# RFID_V2.net
KiCad netlist of a schematic drawn in Altium Designer
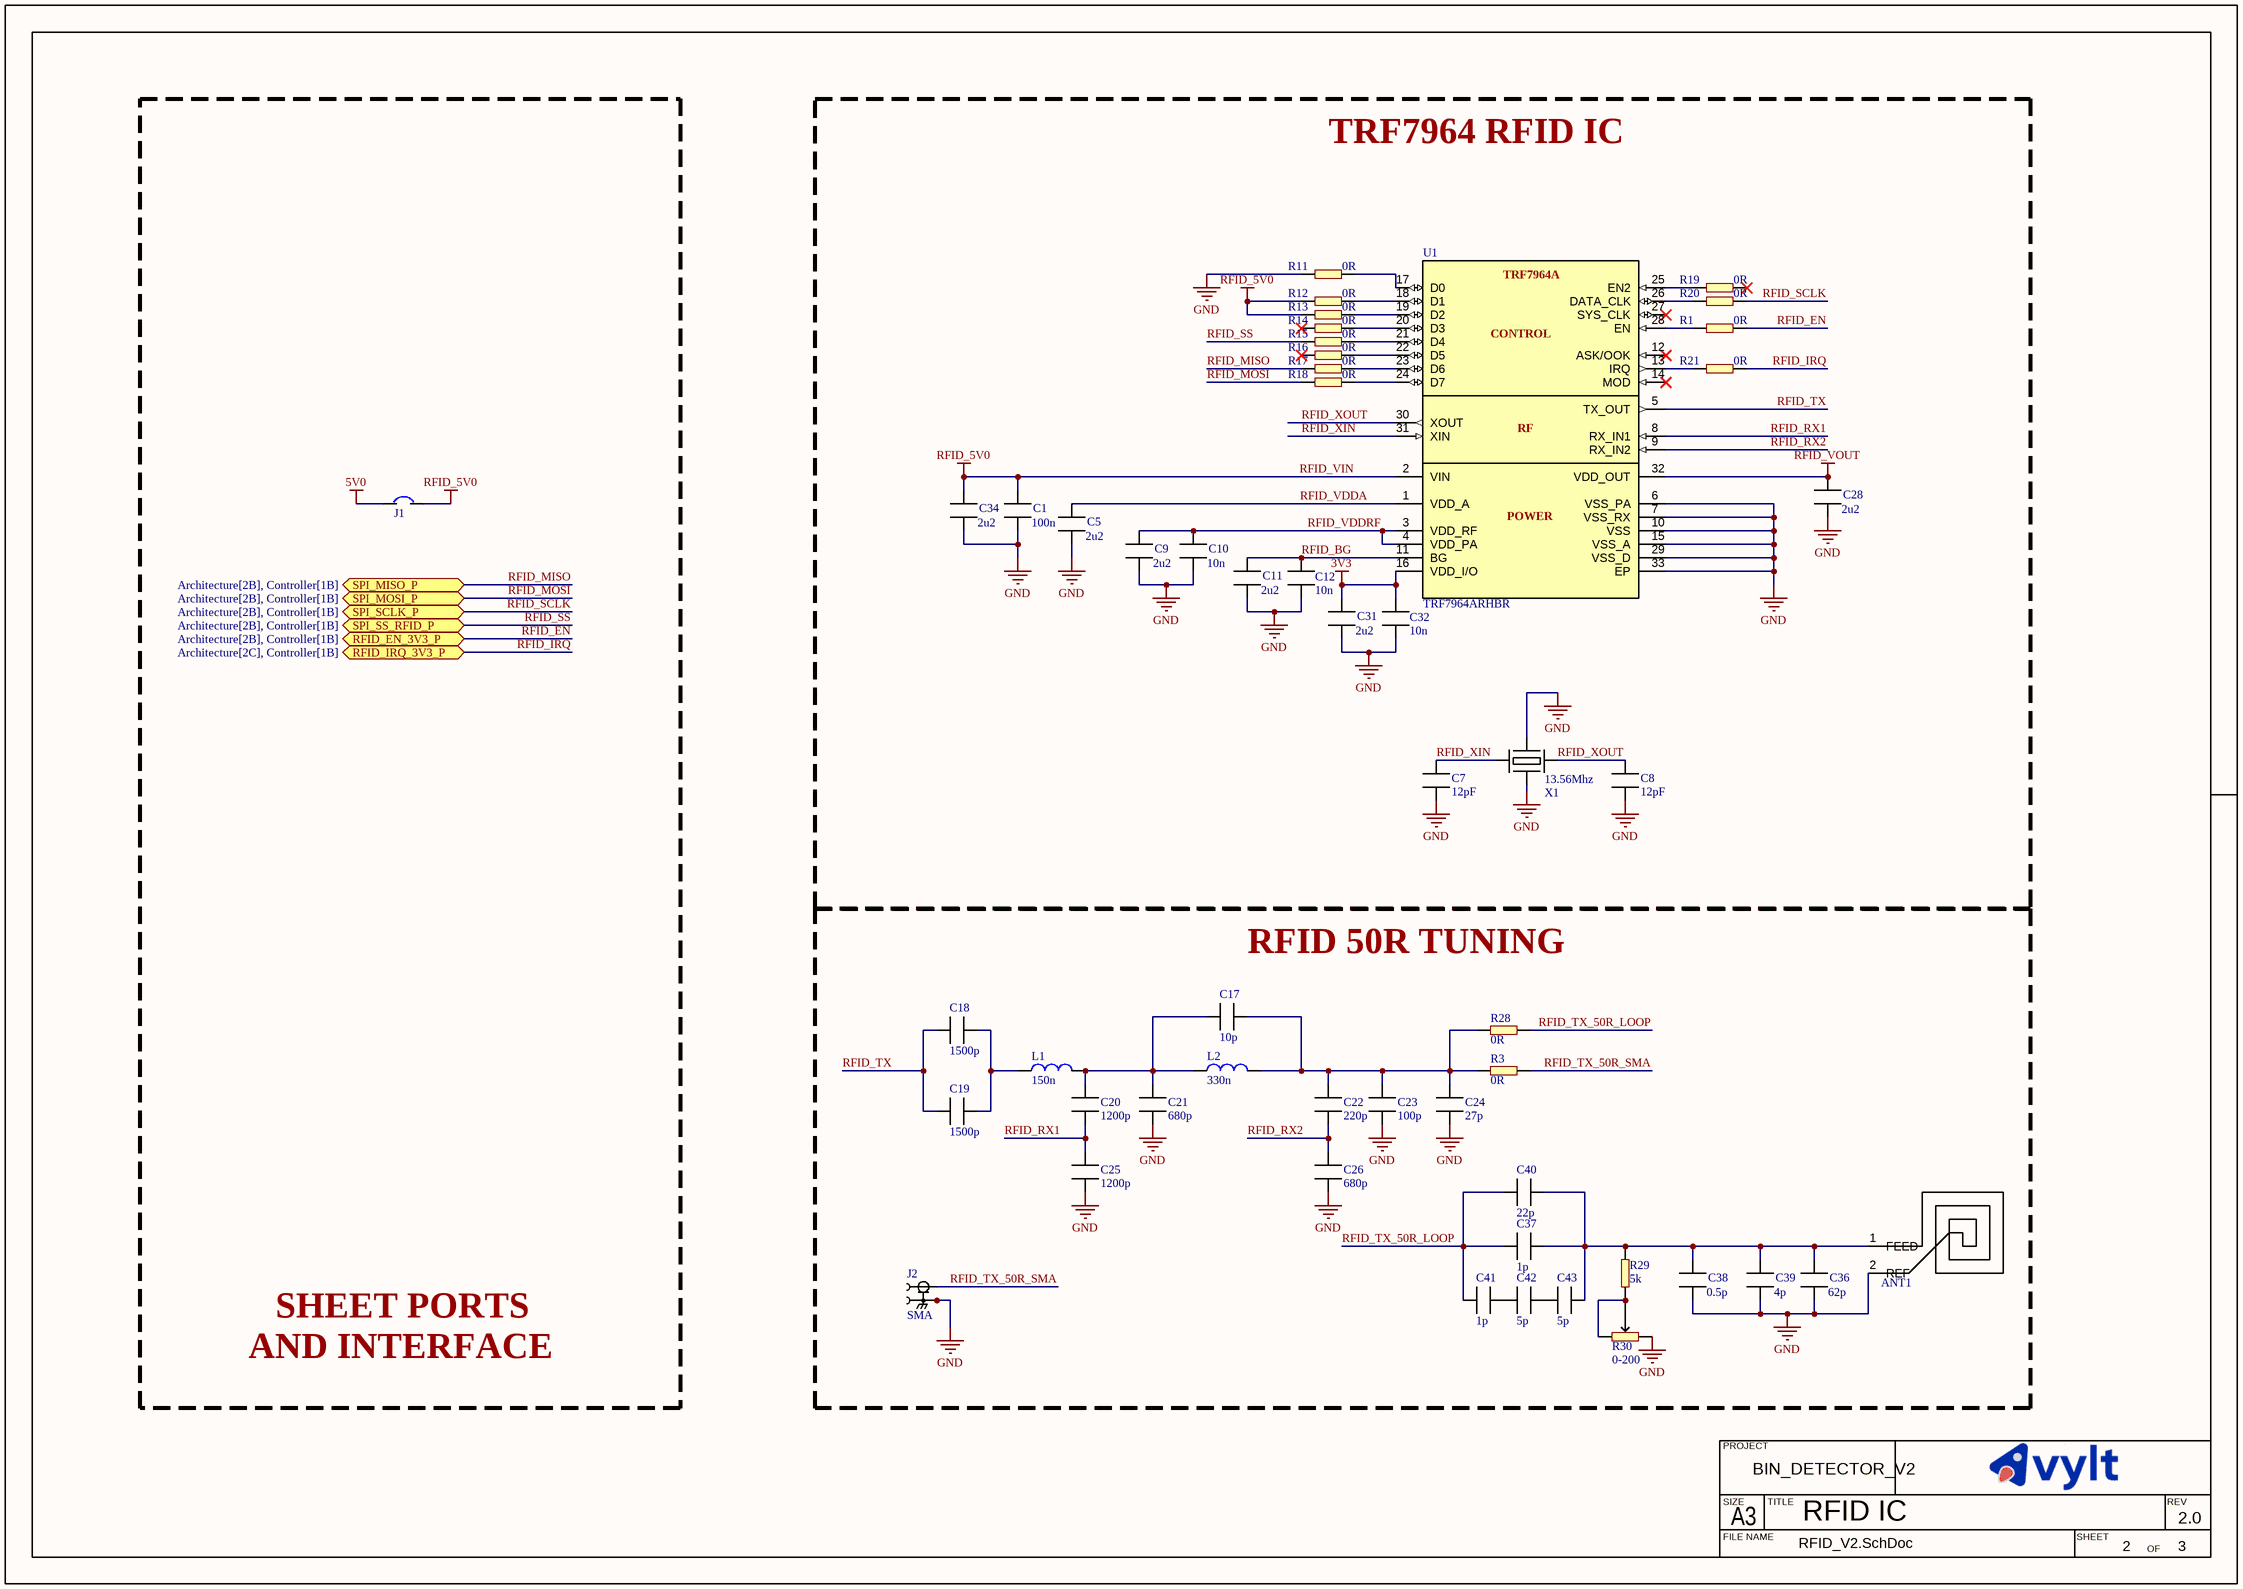
[diagram p0: RFID_V2.SchDoc]

(export (version "E")
  (design (tool "Eeschema 10.0.6"))
  (components
    (comp (ref "ANT1")
      (value "LOOP_ANT_1.51uH")
      (footprint "LOOP_ANT_1.51uH")
      (description "LOOP_ANT_1.51uH_4t_40L_45W_0.4W_0.8P")
      (libsource (lib "Antenna") (part "LOOP_ANT_1.51uH"))
    )
    (comp (ref "C1")
      (value "100n")
      (footprint "CAPC1608X10N")
      (description "MLCC 0603")
      (fields (field (name "Comment") "ERP_102-1"))
      (libsource (lib "Capacitor") (part "MLCC_0603"))
    )
    (comp (ref "C5")
      (value "2u2")
      (footprint "CAPC1608X10N")
      (description "MLCC 0603")
      (fields (field (name "Comment") "ERP_102-1"))
      (libsource (lib "Capacitor") (part "MLCC_0603"))
    )
    (comp (ref "C7")
      (value "12pF")
      (footprint "CAPC1608X10N")
      (description "MLCC 0603")
      (fields (field (name "Comment") "ERP_102-1"))
      (libsource (lib "Capacitor") (part "MLCC_0603"))
    )
    (comp (ref "C8")
      (value "12pF")
      (footprint "CAPC1608X10N")
      (description "MLCC 0603")
      (fields (field (name "Comment") "ERP_102-1"))
      (libsource (lib "Capacitor") (part "MLCC_0603"))
    )
    (comp (ref "C9")
      (value "2u2")
      (footprint "CAPC1608X10N")
      (description "MLCC 0603")
      (fields (field (name "Comment") "ERP_102-1"))
      (libsource (lib "Capacitor") (part "MLCC_0603"))
    )
    (comp (ref "C10")
      (value "10n")
      (footprint "CAPC1608X10N")
      (description "MLCC 0603")
      (fields (field (name "Comment") "ERP_102-1"))
      (libsource (lib "Capacitor") (part "MLCC_0603"))
    )
    (comp (ref "C11")
      (value "2u2")
      (footprint "CAPC1608X10N")
      (description "MLCC 0603")
      (fields (field (name "Comment") "ERP_102-1"))
      (libsource (lib "Capacitor") (part "MLCC_0603"))
    )
    (comp (ref "C12")
      (value "10n")
      (footprint "CAPC1608X10N")
      (description "MLCC 0603")
      (fields (field (name "Comment") "ERP_102-1"))
      (libsource (lib "Capacitor") (part "MLCC_0603"))
    )
    (comp (ref "C17")
      (value "10p")
      (footprint "CAPC1608X10N")
      (description "MLCC 0603")
      (fields (field (name "Comment") "ERP_102-1"))
      (libsource (lib "Capacitor") (part "MLCC_0603"))
    )
    (comp (ref "C18")
      (value "1500p")
      (footprint "CAPC1608X10N")
      (description "MLCC 0603")
      (fields (field (name "Comment") "ERP_102-1"))
      (libsource (lib "Capacitor") (part "MLCC_0603"))
    )
    (comp (ref "C19")
      (value "1500p")
      (footprint "CAPC1608X10N")
      (description "MLCC 0603")
      (fields (field (name "Comment") "ERP_102-1"))
      (libsource (lib "Capacitor") (part "MLCC_0603"))
    )
    (comp (ref "C20")
      (value "1200p")
      (footprint "CAPC1608X10N")
      (description "MLCC 0603")
      (fields (field (name "Comment") "ERP_102-1"))
      (libsource (lib "Capacitor") (part "MLCC_0603"))
    )
    (comp (ref "C21")
      (value "680p")
      (footprint "CAPC1608X10N")
      (description "MLCC 0603")
      (fields (field (name "Comment") "ERP_102-1"))
      (libsource (lib "Capacitor") (part "MLCC_0603"))
    )
    (comp (ref "C22")
      (value "220p")
      (footprint "CAPC1608X10N")
      (description "MLCC 0603")
      (fields (field (name "Comment") "ERP_102-1"))
      (libsource (lib "Capacitor") (part "MLCC_0603"))
    )
    (comp (ref "C23")
      (value "100p")
      (footprint "CAPC1608X10N")
      (description "MLCC 0603")
      (fields (field (name "Comment") "ERP_102-1"))
      (libsource (lib "Capacitor") (part "MLCC_0603"))
    )
    (comp (ref "C24")
      (value "27p")
      (footprint "CAPC1608X10N")
      (description "MLCC 0603")
      (fields (field (name "Comment") "ERP_102-1"))
      (libsource (lib "Capacitor") (part "MLCC_0603"))
    )
    (comp (ref "C25")
      (value "1200p")
      (footprint "CAPC1608X10N")
      (description "MLCC 0603")
      (fields (field (name "Comment") "ERP_102-1"))
      (libsource (lib "Capacitor") (part "MLCC_0603"))
    )
    (comp (ref "C26")
      (value "680p")
      (footprint "CAPC1608X10N")
      (description "MLCC 0603")
      (fields (field (name "Comment") "ERP_102-1"))
      (libsource (lib "Capacitor") (part "MLCC_0603"))
    )
    (comp (ref "C28")
      (value "2u2")
      (footprint "CAPC1608X10N")
      (description "MLCC 0603")
      (fields (field (name "Comment") "ERP_102-1"))
      (libsource (lib "Capacitor") (part "MLCC_0603"))
    )
    (comp (ref "C31")
      (value "2u2")
      (footprint "CAPC1608X10N")
      (description "MLCC 0603")
      (fields (field (name "Comment") "ERP_102-1"))
      (libsource (lib "Capacitor") (part "MLCC_0603"))
    )
    (comp (ref "C32")
      (value "10n")
      (footprint "CAPC1608X10N")
      (description "MLCC 0603")
      (fields (field (name "Comment") "ERP_102-1"))
      (libsource (lib "Capacitor") (part "MLCC_0603"))
    )
    (comp (ref "C34")
      (value "2u2")
      (footprint "CAPC1608X10N")
      (description "MLCC 0603")
      (fields (field (name "Comment") "ERP_102-1"))
      (libsource (lib "Capacitor") (part "MLCC_0603"))
    )
    (comp (ref "C36")
      (value "62p")
      (footprint "CAPC1608X10N")
      (description "Chip Capacitor, 2-Leads, Body 1.60x0.80mm, IPC Medium Density")
      (fields (field (name "Comment") "ERP_102-1"))
      (libsource (lib "Capacitor") (part "MLCC_0603"))
    )
    (comp (ref "C37")
      (value "1p")
      (footprint "CAPC1608X10N")
      (description "Chip Capacitor, 2-Leads, Body 1.60x0.80mm, IPC Medium Density")
      (fields (field (name "Comment") "ERP_102-1"))
      (libsource (lib "Capacitor") (part "MLCC_0603"))
    )
    (comp (ref "C38")
      (value "0.5p")
      (footprint "CAPC1608X10N")
      (description "Chip Capacitor, 2-Leads, Body 1.60x0.80mm, IPC Medium Density")
      (fields (field (name "Comment") "ERP_102-1"))
      (libsource (lib "Capacitor") (part "MLCC_0603"))
    )
    (comp (ref "C39")
      (value "4p")
      (footprint "CAPC1608X10N")
      (description "Chip Capacitor, 2-Leads, Body 1.60x0.80mm, IPC Medium Density")
      (fields (field (name "Comment") "ERP_102-1"))
      (libsource (lib "Capacitor") (part "MLCC_0603"))
    )
    (comp (ref "C40")
      (value "22p")
      (footprint "CAPC1608X10N")
      (description "Chip Capacitor, 2-Leads, Body 1.60x0.80mm, IPC Medium Density")
      (fields (field (name "Comment") "ERP_102-1"))
      (libsource (lib "Capacitor") (part "MLCC_0603"))
    )
    (comp (ref "C41")
      (value "1p")
      (footprint "CAPC1608X10N")
      (description "Chip Capacitor, 2-Leads, Body 1.60x0.80mm, IPC Medium Density")
      (fields (field (name "Comment") "ERP_102-1"))
      (libsource (lib "Capacitor") (part "MLCC_0603"))
    )
    (comp (ref "C42")
      (value "5p")
      (footprint "CAPC1608X10N")
      (description "Chip Capacitor, 2-Leads, Body 1.60x0.80mm, IPC Medium Density")
      (fields (field (name "Comment") "ERP_102-1"))
      (libsource (lib "Capacitor") (part "MLCC_0603"))
    )
    (comp (ref "C43")
      (value "5p")
      (footprint "CAPC1608X10N")
      (description "Chip Capacitor, 2-Leads, Body 1.60x0.80mm, IPC Medium Density")
      (fields (field (name "Comment") "ERP_102-1"))
      (libsource (lib "Capacitor") (part "MLCC_0603"))
    )
    (comp (ref "J1")
      (value "Jumper_2P")
      (footprint "Jumper_2P")
      (description "Jumper 2 Pins")
      (libsource (lib "Jumper") (part "Jumper_2P"))
    )
    (comp (ref "J2")
      (value "SMA")
      (footprint "SMA_TopEntry_50R")
      (description "SMA STR PCB SKT GZD")
      (fields (field (name "Comment") "SMA_TopEntry_50R"))
      (libsource (lib "RF_Connector") (part "SMA_TopEntry_50R"))
    )
    (comp (ref "L1")
      (value "150n")
      (footprint "IND_1008")
      (description "IND_1008")
      (fields (field (name "Comment") "ERP_103-3"))
      (libsource (lib "Inductor") (part "IND_1008"))
    )
    (comp (ref "L2")
      (value "330n")
      (footprint "IND_1008")
      (description "IND_1008")
      (fields (field (name "Comment") "ERP_103-3"))
      (libsource (lib "Inductor") (part "IND_1008"))
    )
    (comp (ref "R1")
      (value "0R")
      (footprint "RES_0603")
      (description "RES_0603")
      (fields (field (name "Comment") "ERP_101-1"))
      (libsource (lib "Resistor") (part "RES_0603"))
    )
    (comp (ref "R3")
      (value "0R")
      (footprint "RES_0603")
      (description "RES_0603")
      (fields (field (name "Comment") "ERP_101-1"))
      (libsource (lib "Resistor") (part "RES_0603"))
    )
    (comp (ref "R11")
      (value "0R")
      (footprint "RES_0603")
      (description "RES_0603")
      (fields (field (name "Comment") "ERP_101-1"))
      (libsource (lib "Resistor") (part "RES_0603"))
    )
    (comp (ref "R12")
      (value "0R")
      (footprint "RES_0603")
      (description "RES_0603")
      (fields (field (name "Comment") "ERP_101-1"))
      (libsource (lib "Resistor") (part "RES_0603"))
    )
    (comp (ref "R13")
      (value "0R")
      (footprint "RES_0603")
      (description "RES_0603")
      (fields (field (name "Comment") "ERP_101-1"))
      (libsource (lib "Resistor") (part "RES_0603"))
    )
    (comp (ref "R14")
      (value "0R")
      (footprint "RES_0603")
      (description "RES_0603")
      (fields (field (name "Comment") "ERP_101-1"))
      (libsource (lib "Resistor") (part "RES_0603"))
    )
    (comp (ref "R15")
      (value "0R")
      (footprint "RES_0603")
      (description "RES_0603")
      (fields (field (name "Comment") "ERP_101-1"))
      (libsource (lib "Resistor") (part "RES_0603"))
    )
    (comp (ref "R16")
      (value "0R")
      (footprint "RES_0603")
      (description "RES_0603")
      (fields (field (name "Comment") "ERP_101-1"))
      (libsource (lib "Resistor") (part "RES_0603"))
    )
    (comp (ref "R17")
      (value "0R")
      (footprint "RES_0603")
      (description "RES_0603")
      (fields (field (name "Comment") "ERP_101-1"))
      (libsource (lib "Resistor") (part "RES_0603"))
    )
    (comp (ref "R18")
      (value "0R")
      (footprint "RES_0603")
      (description "RES_0603")
      (fields (field (name "Comment") "ERP_101-1"))
      (libsource (lib "Resistor") (part "RES_0603"))
    )
    (comp (ref "R19")
      (value "0R")
      (footprint "RES_0603")
      (description "RES_0603")
      (fields (field (name "Comment") "ERP_101-1"))
      (libsource (lib "Resistor") (part "RES_0603"))
    )
    (comp (ref "R20")
      (value "0R")
      (footprint "RES_0603")
      (description "RES_0603")
      (fields (field (name "Comment") "ERP_101-1"))
      (libsource (lib "Resistor") (part "RES_0603"))
    )
    (comp (ref "R21")
      (value "0R")
      (footprint "RES_0603")
      (description "RES_0603")
      (fields (field (name "Comment") "ERP_101-1"))
      (libsource (lib "Resistor") (part "RES_0603"))
    )
    (comp (ref "R28")
      (value "0R")
      (footprint "RES_0603")
      (description "RES_0603")
      (fields (field (name "Comment") "ERP_101-1"))
      (libsource (lib "Resistor") (part "RES_0603"))
    )
    (comp (ref "R29")
      (value "5k")
      (footprint "RES_0603")
      (description "RES_0603")
      (fields (field (name "Comment") "ERP_101-1"))
      (libsource (lib "") (part "RES_0603_1"))
    )
    (comp (ref "R30")
      (value "0-200")
      (footprint "RES_VAR_3361P")
      (description "TRIMMER 200 OHM 0.5W GW TOP ADJ")
      (fields (field (name "Comment") "ERP_101-1"))
      (libsource (lib "Resistor") (part "RES_VAR_3361P"))
    )
    (comp (ref "U1")
      (value "TRF7964ARHBR")
      (footprint "RHB32_3P45X3P45_TEX")
      (description "IC RFID READER 13.56MHZ 32VQFN")
      (fields (field (name "Comment") "ERP_121-4"))
      (libsource (lib "RF-IC") (part "TRF7964A"))
    )
    (comp (ref "X1")
      (value "13.56Mhz")
      (footprint "CRYS_L3.2_W2.5")
      (description "CRYS_L3.2_W2.5")
      (fields (field (name "Comment") "ERP_111-1"))
      (libsource (lib "Crystal") (part "CRYS_L3.2_W2.5"))
    )
  )
  (nets
    (net (code "1") (name "/RFID_BG") (class "Default")
      (node (ref "C11") (pin "1") (pinfunction "1_1") (pintype "passive"))
      (node (ref "C12") (pin "1") (pinfunction "1_1") (pintype "passive"))
      (node (ref "U1") (pin "11") (pinfunction "BG_11") (pintype "passive"))
    )
    (net (code "2") (name "/RFID_EN") (class "Default")
      (node (ref "R1") (pin "1") (pinfunction "1_1") (pintype "passive"))
    )
    (net (code "3") (name "/RFID_IRQ") (class "Default")
      (node (ref "R21") (pin "1") (pinfunction "1_1") (pintype "passive"))
    )
    (net (code "4") (name "/RFID_MISO") (class "Default")
      (node (ref "R17") (pin "2") (pinfunction "2_2") (pintype "passive"))
    )
    (net (code "5") (name "/RFID_MOSI") (class "Default")
      (node (ref "R18") (pin "2") (pinfunction "2_2") (pintype "passive"))
    )
    (net (code "6") (name "/RFID_RX1") (class "Default")
      (node (ref "C20") (pin "1") (pinfunction "1_1") (pintype "passive"))
      (node (ref "C25") (pin "2") (pinfunction "2_2") (pintype "passive"))
      (node (ref "U1") (pin "8") (pinfunction "RX_IN1_8") (pintype "input"))
    )
    (net (code "7") (name "/RFID_RX2") (class "Default")
      (node (ref "C22") (pin "1") (pinfunction "1_1") (pintype "passive"))
      (node (ref "C26") (pin "2") (pinfunction "2_2") (pintype "passive"))
      (node (ref "U1") (pin "9") (pinfunction "RX_IN2_9") (pintype "input"))
    )
    (net (code "8") (name "/RFID_SCLK") (class "Default")
      (node (ref "R20") (pin "1") (pinfunction "1_1") (pintype "passive"))
    )
    (net (code "9") (name "/RFID_SS") (class "Default")
      (node (ref "R15") (pin "2") (pinfunction "2_2") (pintype "passive"))
    )
    (net (code "10") (name "/RFID_TX") (class "Default")
      (node (ref "C18") (pin "1") (pinfunction "1_1") (pintype "passive"))
      (node (ref "C19") (pin "1") (pinfunction "1_1") (pintype "passive"))
      (node (ref "U1") (pin "5") (pinfunction "TX_OUT_5") (pintype "output"))
    )
    (net (code "11") (name "/RFID_TX_50R_LOOP") (class "Default")
      (node (ref "C37") (pin "1") (pinfunction "1_1") (pintype "passive"))
      (node (ref "C40") (pin "1") (pinfunction "1_1") (pintype "passive"))
      (node (ref "C41") (pin "1") (pinfunction "1_1") (pintype "passive"))
      (node (ref "R28") (pin "1") (pinfunction "1_1") (pintype "passive"))
    )
    (net (code "12") (name "/RFID_TX_50R_SMA") (class "Default")
      (node (ref "J2") (pin "1") (pinfunction "1_1") (pintype "passive"))
      (node (ref "R3") (pin "1") (pinfunction "1_1") (pintype "passive"))
    )
    (net (code "13") (name "/RFID_VDDA") (class "Default")
      (node (ref "C5") (pin "1") (pinfunction "1_1") (pintype "passive"))
      (node (ref "U1") (pin "1") (pinfunction "VDD_A_1") (pintype "passive"))
    )
    (net (code "14") (name "/RFID_VDDRF") (class "Default")
      (node (ref "C10") (pin "1") (pinfunction "1_1") (pintype "passive"))
      (node (ref "C9") (pin "1") (pinfunction "1_1") (pintype "passive"))
      (node (ref "U1") (pin "3") (pinfunction "VDD_RF_3") (pintype "passive"))
      (node (ref "U1") (pin "4") (pinfunction "VDD_PA_4") (pintype "passive"))
    )
    (net (code "15") (name "/RFID_XIN") (class "Default")
      (node (ref "C7") (pin "1") (pinfunction "1_1") (pintype "passive"))
      (node (ref "U1") (pin "31") (pinfunction "XIN_31") (pintype "input"))
      (node (ref "X1") (pin "1") (pinfunction "1_1") (pintype "passive"))
    )
    (net (code "16") (name "/RFID_XOUT") (class "Default")
      (node (ref "C8") (pin "1") (pinfunction "1_1") (pintype "passive"))
      (node (ref "U1") (pin "30") (pinfunction "XOUT_30") (pintype "output"))
      (node (ref "X1") (pin "3") (pinfunction "3_3") (pintype "passive"))
    )
    (net (code "17") (name "3V3") (class "Default")
      (node (ref "C31") (pin "1") (pinfunction "1_1") (pintype "passive"))
      (node (ref "C32") (pin "1") (pinfunction "1_1") (pintype "passive"))
      (node (ref "U1") (pin "16") (pinfunction "VDD_I/O_16") (pintype "passive"))
    )
    (net (code "18") (name "5V0") (class "Default") (node (ref "J1") (pin "1") (pintype "passive")))
    (net (code "19") (name "GND") (class "Default")
      (node (ref "ANT1") (pin "2") (pinfunction "REF_2") (pintype "passive"))
      (node (ref "C1") (pin "2") (pinfunction "2_2") (pintype "passive"))
      (node (ref "C10") (pin "2") (pinfunction "2_2") (pintype "passive"))
      (node (ref "C11") (pin "2") (pinfunction "2_2") (pintype "passive"))
      (node (ref "C12") (pin "2") (pinfunction "2_2") (pintype "passive"))
      (node (ref "C21") (pin "1") (pinfunction "1_1") (pintype "passive"))
      (node (ref "C23") (pin "1") (pinfunction "1_1") (pintype "passive"))
      (node (ref "C24") (pin "1") (pinfunction "1_1") (pintype "passive"))
      (node (ref "C25") (pin "1") (pinfunction "1_1") (pintype "passive"))
      (node (ref "C26") (pin "1") (pinfunction "1_1") (pintype "passive"))
      (node (ref "C28") (pin "2") (pinfunction "2_2") (pintype "passive"))
      (node (ref "C31") (pin "2") (pinfunction "2_2") (pintype "passive"))
      (node (ref "C32") (pin "2") (pinfunction "2_2") (pintype "passive"))
      (node (ref "C34") (pin "2") (pinfunction "2_2") (pintype "passive"))
      (node (ref "C36") (pin "2") (pinfunction "2_2") (pintype "passive"))
      (node (ref "C38") (pin "2") (pinfunction "2_2") (pintype "passive"))
      (node (ref "C39") (pin "2") (pinfunction "2_2") (pintype "passive"))
      (node (ref "C5") (pin "2") (pinfunction "2_2") (pintype "passive"))
      (node (ref "C7") (pin "2") (pinfunction "2_2") (pintype "passive"))
      (node (ref "C8") (pin "2") (pinfunction "2_2") (pintype "passive"))
      (node (ref "C9") (pin "2") (pinfunction "2_2") (pintype "passive"))
      (node (ref "J2") (pin "2") (pinfunction "2_2") (pintype "passive"))
      (node (ref "J2") (pin "3") (pinfunction "3_3") (pintype "passive"))
      (node (ref "J2") (pin "4") (pinfunction "4_4") (pintype "passive"))
      (node (ref "J2") (pin "5") (pinfunction "5_5") (pintype "passive"))
      (node (ref "R11") (pin "2") (pinfunction "2_2") (pintype "passive"))
      (node (ref "R30") (pin "1") (pinfunction "1_1") (pintype "passive"))
      (node (ref "U1") (pin "10") (pinfunction "VSS_10") (pintype "passive"))
      (node (ref "U1") (pin "15") (pinfunction "VSS_A_15") (pintype "passive"))
      (node (ref "U1") (pin "29") (pinfunction "VSS_D_29") (pintype "passive"))
      (node (ref "U1") (pin "33") (pinfunction "EP_33") (pintype "passive"))
      (node (ref "U1") (pin "6") (pinfunction "VSS_PA_6") (pintype "passive"))
      (node (ref "U1") (pin "7") (pinfunction "VSS_RX_7") (pintype "passive"))
      (node (ref "X1") (pin "2") (pinfunction "2_2") (pintype "passive"))
      (node (ref "X1") (pin "4") (pinfunction "4_4") (pintype "passive"))
    )
    (net (code "20") (name "Net-(ANT1-FEED)") (class "Default")
      (node (ref "ANT1") (pin "1") (pinfunction "FEED_1") (pintype "passive"))
      (node (ref "C36") (pin "1") (pinfunction "1_1") (pintype "passive"))
      (node (ref "C37") (pin "2") (pinfunction "2_2") (pintype "passive"))
      (node (ref "C38") (pin "1") (pinfunction "1_1") (pintype "passive"))
      (node (ref "C39") (pin "1") (pinfunction "1_1") (pintype "passive"))
      (node (ref "C40") (pin "2") (pinfunction "2_2") (pintype "passive"))
      (node (ref "C43") (pin "2") (pinfunction "2_2") (pintype "passive"))
      (node (ref "R29") (pin "2") (pinfunction "2_2") (pintype "passive"))
    )
    (net (code "21") (name "Net-(C17-Pad1)") (class "Default")
      (node (ref "C17") (pin "1") (pinfunction "1_1") (pintype "passive"))
      (node (ref "C22") (pin "2") (pinfunction "2_2") (pintype "passive"))
      (node (ref "C23") (pin "2") (pinfunction "2_2") (pintype "passive"))
      (node (ref "C24") (pin "2") (pinfunction "2_2") (pintype "passive"))
      (node (ref "L2") (pin "2") (pinfunction "2_2") (pintype "passive"))
      (node (ref "R28") (pin "2") (pinfunction "2_2") (pintype "passive"))
      (node (ref "R3") (pin "2") (pinfunction "2_2") (pintype "passive"))
    )
    (net (code "22") (name "Net-(C17-Pad2)") (class "Default")
      (node (ref "C17") (pin "2") (pinfunction "2_2") (pintype "passive"))
      (node (ref "C20") (pin "2") (pinfunction "2_2") (pintype "passive"))
      (node (ref "C21") (pin "2") (pinfunction "2_2") (pintype "passive"))
      (node (ref "L1") (pin "2") (pinfunction "2_2") (pintype "passive"))
      (node (ref "L2") (pin "1") (pinfunction "1_1") (pintype "passive"))
    )
    (net (code "23") (name "Net-(C18-Pad2)") (class "Default")
      (node (ref "C18") (pin "2") (pinfunction "2_2") (pintype "passive"))
      (node (ref "C19") (pin "2") (pinfunction "2_2") (pintype "passive"))
      (node (ref "L1") (pin "1") (pinfunction "1_1") (pintype "passive"))
    )
    (net (code "24") (name "Net-(C41-Pad2)") (class "Default")
      (node (ref "C41") (pin "2") (pinfunction "2_2") (pintype "passive"))
      (node (ref "C42") (pin "1") (pinfunction "1_1") (pintype "passive"))
    )
    (net (code "25") (name "Net-(C42-Pad2)") (class "Default")
      (node (ref "C42") (pin "2") (pinfunction "2_2") (pintype "passive"))
      (node (ref "C43") (pin "1") (pinfunction "1_1") (pintype "passive"))
    )
    (net (code "26") (name "Net-(R29-Pad1)") (class "Default")
      (node (ref "R29") (pin "1") (pinfunction "1_1") (pintype "passive"))
      (node (ref "R30") (pin "2") (pinfunction "2_2") (pintype "passive"))
      (node (ref "R30") (pin "3") (pinfunction "3_3") (pintype "passive"))
    )
    (net (code "27") (name "Net-(U1-D0)") (class "Default")
      (node (ref "R11") (pin "1") (pinfunction "1_1") (pintype "passive"))
      (node (ref "U1") (pin "17") (pinfunction "D0_17") (pintype "bidirectional"))
    )
    (net (code "28") (name "Net-(U1-D1)") (class "Default")
      (node (ref "R12") (pin "1") (pinfunction "1_1") (pintype "passive"))
      (node (ref "U1") (pin "18") (pinfunction "D1_18") (pintype "bidirectional"))
    )
    (net (code "29") (name "Net-(U1-D2)") (class "Default")
      (node (ref "R13") (pin "1") (pinfunction "1_1") (pintype "passive"))
      (node (ref "U1") (pin "19") (pinfunction "D2_19") (pintype "bidirectional"))
    )
    (net (code "30") (name "Net-(U1-D3)") (class "Default")
      (node (ref "R14") (pin "1") (pinfunction "1_1") (pintype "passive"))
      (node (ref "U1") (pin "20") (pinfunction "D3_20") (pintype "bidirectional"))
    )
    (net (code "31") (name "Net-(U1-D4)") (class "Default")
      (node (ref "R15") (pin "1") (pinfunction "1_1") (pintype "passive"))
      (node (ref "U1") (pin "21") (pinfunction "D4_21") (pintype "bidirectional"))
    )
    (net (code "32") (name "Net-(U1-D5)") (class "Default")
      (node (ref "R16") (pin "1") (pinfunction "1_1") (pintype "passive"))
      (node (ref "U1") (pin "22") (pinfunction "D5_22") (pintype "bidirectional"))
    )
    (net (code "33") (name "Net-(U1-D6)") (class "Default")
      (node (ref "R17") (pin "1") (pinfunction "1_1") (pintype "passive"))
      (node (ref "U1") (pin "23") (pinfunction "D6_23") (pintype "bidirectional"))
    )
    (net (code "34") (name "Net-(U1-D7)") (class "Default")
      (node (ref "R18") (pin "1") (pinfunction "1_1") (pintype "passive"))
      (node (ref "U1") (pin "24") (pinfunction "D7_24") (pintype "bidirectional"))
    )
    (net (code "35") (name "Net-(U1-DATA_CLK)") (class "Default")
      (node (ref "R20") (pin "2") (pinfunction "2_2") (pintype "passive"))
      (node (ref "U1") (pin "26") (pinfunction "DATA_CLK_26") (pintype "bidirectional"))
    )
    (net (code "36") (name "Net-(U1-EN)") (class "Default")
      (node (ref "R1") (pin "2") (pinfunction "2_2") (pintype "passive"))
      (node (ref "U1") (pin "28") (pinfunction "EN_28") (pintype "input"))
    )
    (net (code "37") (name "Net-(U1-EN2)") (class "Default")
      (node (ref "R19") (pin "2") (pinfunction "2_2") (pintype "passive"))
      (node (ref "U1") (pin "25") (pinfunction "EN2_25") (pintype "input"))
    )
    (net (code "38") (name "Net-(U1-IRQ)") (class "Default")
      (node (ref "R21") (pin "2") (pinfunction "2_2") (pintype "passive"))
      (node (ref "U1") (pin "13") (pinfunction "IRQ_13") (pintype "output"))
    )
    (net (code "39") (name "RFID_5V0") (class "Default")
      (node (ref "C1") (pin "1") (pinfunction "1_1") (pintype "passive"))
      (node (ref "C34") (pin "1") (pinfunction "1_1") (pintype "passive"))
      (node (ref "J1") (pin "2") (pintype "passive"))
      (node (ref "R12") (pin "2") (pinfunction "2_2") (pintype "passive"))
      (node (ref "R13") (pin "2") (pinfunction "2_2") (pintype "passive"))
      (node (ref "U1") (pin "2") (pinfunction "VIN_2") (pintype "passive"))
    )
    (net (code "40") (name "RFID_VOUT") (class "Default")
      (node (ref "C28") (pin "1") (pinfunction "1_1") (pintype "passive"))
      (node (ref "U1") (pin "32") (pinfunction "VDD_OUT_32") (pintype "passive"))
    )
    (net (code "41") (name "unconnected-(R14-Pad2)") (class "Default")
      (node (ref "R14") (pin "2") (pinfunction "2_2") (pintype "passive+no_connect"))
    )
    (net (code "42") (name "unconnected-(R16-Pad2)") (class "Default")
      (node (ref "R16") (pin "2") (pinfunction "2_2") (pintype "passive+no_connect"))
    )
    (net (code "43") (name "unconnected-(R19-Pad1)") (class "Default")
      (node (ref "R19") (pin "1") (pinfunction "1_1") (pintype "passive+no_connect"))
    )
    (net (code "44") (name "unconnected-(U1-ASK{slash}OOK-Pad12)") (class "Default")
      (node (ref "U1") (pin "12") (pinfunction "ASK/OOK_12") (pintype "input+no_connect"))
    )
    (net (code "45") (name "unconnected-(U1-MOD-Pad14)") (class "Default")
      (node (ref "U1") (pin "14") (pinfunction "MOD_14") (pintype "input+no_connect"))
    )
    (net (code "46") (name "unconnected-(U1-SYS_CLK-Pad27)") (class "Default")
      (node (ref "U1") (pin "27") (pinfunction "SYS_CLK_27") (pintype "bidirectional+no_connect"))
    )
  )
)
